# Draft_2.net
KiCad netlist of a schematic drawn in EAGLE
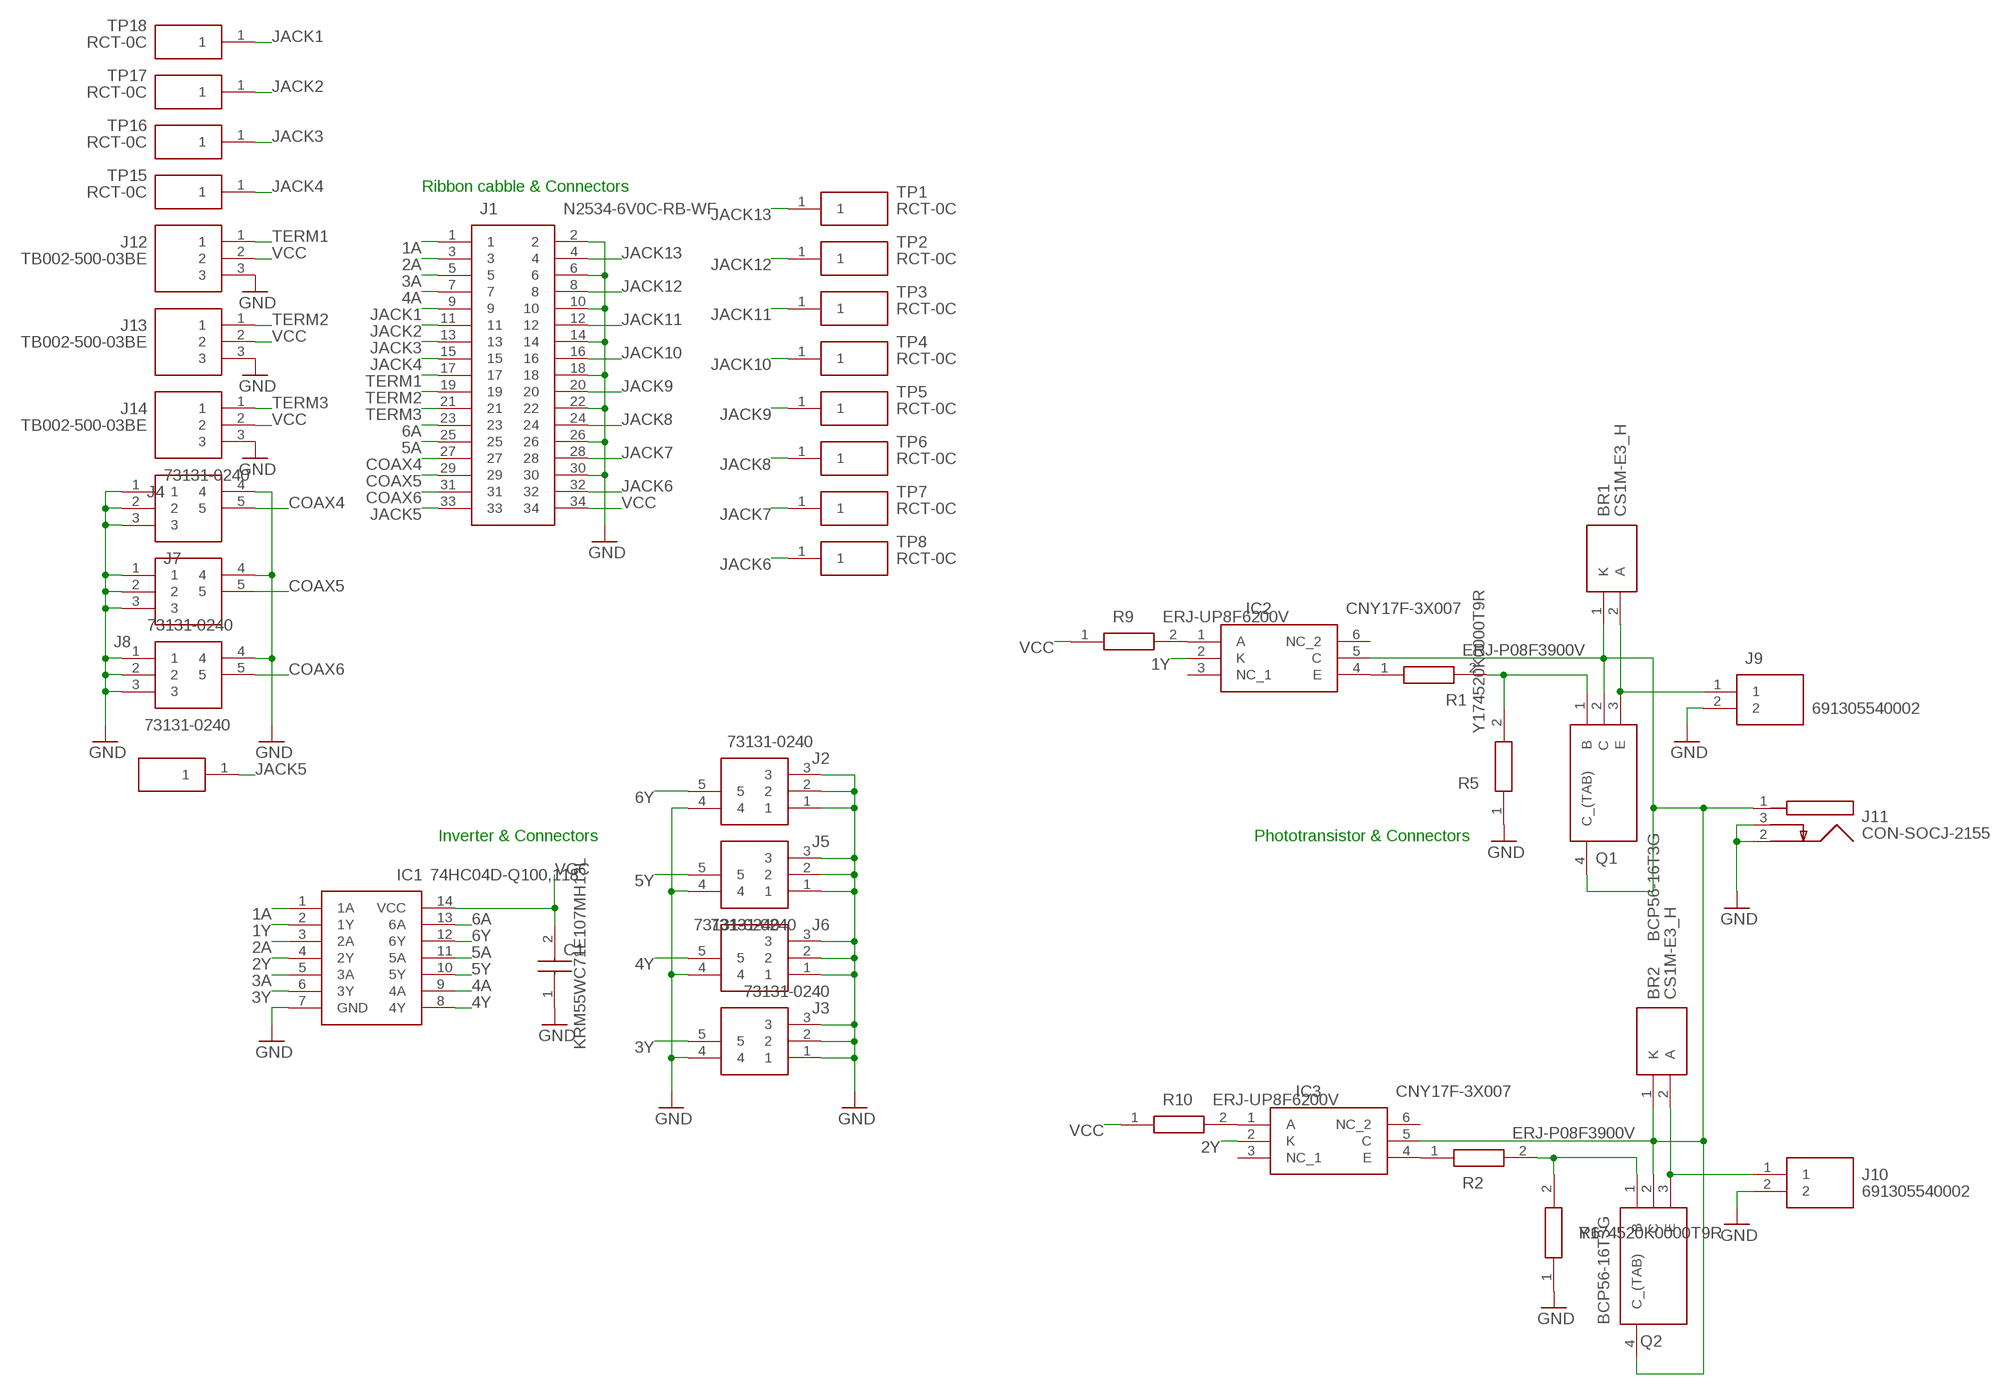
[diagram p0: schematic, sheet 1]

(export (version "E")
  (design (tool "Eeschema 10.0.6"))
  (components
    (comp (ref "BR1")
      (value "CS1M-E3_H")
      (footprint "eagle-import:DIOM5127X229N")
      (fields
        (field (name "MANUFACTURER_PART_NUMBER") "CS1M-E3/H")
        (field (name "MOUSER_PART_NUMBER") "78-CS1M-E3/H")
      )
      (libsource (lib "eagle-import") (part "CS1M-E3_H"))
    )
    (comp (ref "BR2")
      (value "CS1M-E3_H")
      (footprint "eagle-import:DIOM5127X229N")
      (fields
        (field (name "MANUFACTURER_PART_NUMBER") "CS1M-E3/H")
        (field (name "MOUSER_PART_NUMBER") "78-CS1M-E3/H")
      )
      (libsource (lib "eagle-import") (part "CS1M-E3_H"))
    )
    (comp (ref "C1")
      (value "KRM55WC71E107MH13L")
      (footprint "eagle-import:CAPC6153X670N")
      (fields (field (name "MOUSER_PART_NUMBER") "81-KRM55WC71E107MH3L"))
      (libsource (lib "eagle-import") (part "KRM55WC71E107MH13L"))
    )
    (comp (ref "IC1")
      (value "74HC04D-Q100,118")
      (footprint "eagle-import:SOIC127P600X175-14N")
      (fields (field (name "MOUSER_PART_NUMBER") "771-74HC04D-Q100"))
      (libsource (lib "eagle-import") (part "74HC04D-Q100,118"))
    )
    (comp (ref "IC2")
      (value "CNY17F-3X007")
      (footprint "eagle-import:SOP254P1030X440-6N")
      (fields (field (name "MOUSER_PART_NUMBER") "782-CNY17F-3X007"))
      (libsource (lib "eagle-import") (part "CNY17F-3X007"))
    )
    (comp (ref "IC3")
      (value "CNY17F-3X007")
      (footprint "eagle-import:SOP254P1030X440-6N")
      (fields (field (name "MOUSER_PART_NUMBER") "782-CNY17F-3X007"))
      (libsource (lib "eagle-import") (part "CNY17F-3X007"))
    )
    (comp (ref "J1")
      (value "N2534-6V0C-RB-WF")
      (footprint "eagle-import:3M_N2534-6V0C-RB-WF")
      (fields
        (field (name "MOUSER_PART_NUMBER") "517-N2534-6V0C-RB-WF")
        (field (name "RS_PART_NUMBER") "0212650")
      )
      (libsource (lib "eagle-import") (part "N2534-6V0C-RB-WF"))
    )
    (comp (ref "J2")
      (value "73131-0240")
      (footprint "eagle-import:731310240")
      (fields (field (name "MOUSER_PART_NUMBER") "538-73131-0240"))
      (libsource (lib "eagle-import") (part "73131-0240"))
    )
    (comp (ref "J3")
      (value "73131-0240")
      (footprint "eagle-import:731310240")
      (fields (field (name "MOUSER_PART_NUMBER") "538-73131-0240"))
      (libsource (lib "eagle-import") (part "73131-0240"))
    )
    (comp (ref "J4")
      (value "73131-0240")
      (footprint "eagle-import:731310240")
      (fields (field (name "MOUSER_PART_NUMBER") "538-73131-0240"))
      (libsource (lib "eagle-import") (part "73131-0240"))
    )
    (comp (ref "J5")
      (value "73131-0240")
      (footprint "eagle-import:731310240")
      (fields (field (name "MOUSER_PART_NUMBER") "538-73131-0240"))
      (libsource (lib "eagle-import") (part "73131-0240"))
    )
    (comp (ref "J6")
      (value "73131-0240")
      (footprint "eagle-import:731310240")
      (fields (field (name "MOUSER_PART_NUMBER") "538-73131-0240"))
      (libsource (lib "eagle-import") (part "73131-0240"))
    )
    (comp (ref "J7")
      (value "73131-0240")
      (footprint "eagle-import:731310240")
      (fields (field (name "MOUSER_PART_NUMBER") "538-73131-0240"))
      (libsource (lib "eagle-import") (part "73131-0240"))
    )
    (comp (ref "J8")
      (value "73131-0240")
      (footprint "eagle-import:731310240")
      (fields (field (name "MOUSER_PART_NUMBER") "538-73131-0240"))
      (libsource (lib "eagle-import") (part "73131-0240"))
    )
    (comp (ref "J9")
      (value "691305540002")
      (footprint "eagle-import:SHDRRA2W100P0X508_1X2_1216X120")
      (fields (field (name "MOUSER_PART_NUMBER") "710-691305540002"))
      (libsource (lib "eagle-import") (part "691305540002"))
    )
    (comp (ref "J10")
      (value "691305540002")
      (footprint "eagle-import:SHDRRA2W100P0X508_1X2_1216X120")
      (fields (field (name "MOUSER_PART_NUMBER") "710-691305540002"))
      (libsource (lib "eagle-import") (part "691305540002"))
    )
    (comp (ref "J11")
      (value "CON-SOCJ-2155")
      (footprint "eagle-import:CONSOCJ2155")
      (fields (field (name "MOUSER_PART_NUMBER") "992-CON-SOCJ-2155"))
      (libsource (lib "eagle-import") (part "CON-SOCJ-2155"))
    )
    (comp (ref "J12")
      (value "TB002-500-03BE")
      (footprint "eagle-import:SHDR3W100P0X500_1X3_1500X760X1")
      (fields (field (name "MOUSER_PART_NUMBER") "490-TB002-500-03BE"))
      (libsource (lib "eagle-import") (part "TB002-500-03BE"))
    )
    (comp (ref "J13")
      (value "TB002-500-03BE")
      (footprint "eagle-import:SHDR3W100P0X500_1X3_1500X760X1")
      (fields (field (name "MOUSER_PART_NUMBER") "490-TB002-500-03BE"))
      (libsource (lib "eagle-import") (part "TB002-500-03BE"))
    )
    (comp (ref "J14")
      (value "TB002-500-03BE")
      (footprint "eagle-import:SHDR3W100P0X500_1X3_1500X760X1")
      (fields (field (name "MOUSER_PART_NUMBER") "490-TB002-500-03BE"))
      (libsource (lib "eagle-import") (part "TB002-500-03BE"))
    )
    (comp (ref "Q1")
      (value "BCP56-16T3G")
      (footprint "eagle-import:SOT230P700X175-4N")
      (fields
        (field (name "MOUSER_PART_NUMBER") "863-BCP56-16T3G")
        (field (name "RS_PART_NUMBER") "7737633P")
      )
      (libsource (lib "eagle-import") (part "BCP56-16T3G"))
    )
    (comp (ref "Q2")
      (value "BCP56-16T3G")
      (footprint "eagle-import:SOT230P700X175-4N")
      (fields
        (field (name "MOUSER_PART_NUMBER") "863-BCP56-16T3G")
        (field (name "RS_PART_NUMBER") "7737633P")
      )
      (libsource (lib "eagle-import") (part "BCP56-16T3G"))
    )
    (comp (ref "R1")
      (value "ERJ-P08F3900V")
      (footprint "eagle-import:RESC3116X70N")
      (fields (field (name "MOUSER_PART_NUMBER") "667-ERJ-P08F3900V"))
      (libsource (lib "eagle-import") (part "ERJ-P08F3900V"))
    )
    (comp (ref "R2")
      (value "ERJ-P08F3900V")
      (footprint "eagle-import:RESC3116X70N")
      (fields (field (name "MOUSER_PART_NUMBER") "667-ERJ-P08F3900V"))
      (libsource (lib "eagle-import") (part "ERJ-P08F3900V"))
    )
    (comp (ref "R5")
      (value "Y174520K0000T9R")
      (footprint "eagle-import:RESM6032X279N")
      (fields
        (field (name "MOUSER_PART_NUMBER") "71-SMR1DZ20K000TST")
        (field (name "RS_PART_NUMBER") "7637249P")
      )
      (libsource (lib "eagle-import") (part "Y174520K0000T9R"))
    )
    (comp (ref "R6")
      (value "Y174520K0000T9R")
      (footprint "eagle-import:RESM6032X279N")
      (fields
        (field (name "MOUSER_PART_NUMBER") "71-SMR1DZ20K000TST")
        (field (name "RS_PART_NUMBER") "7637249P")
      )
      (libsource (lib "eagle-import") (part "Y174520K0000T9R"))
    )
    (comp (ref "R9")
      (value "ERJ-UP8F6200V")
      (footprint "eagle-import:RESC3116X70N")
      (fields (field (name "MOUSER_PART_NUMBER") "667-ERJ-UP8F6200V"))
      (libsource (lib "eagle-import") (part "ERJ-UP8F6200V"))
    )
    (comp (ref "R10")
      (value "ERJ-UP8F6200V")
      (footprint "eagle-import:RESC3116X70N")
      (fields (field (name "MOUSER_PART_NUMBER") "667-ERJ-UP8F6200V"))
      (libsource (lib "eagle-import") (part "ERJ-UP8F6200V"))
    )
    (comp (ref "TP1")
      (value "RCT-0C")
      (footprint "eagle-import:RCT-0C")
      (fields (field (name "MOUSER_PART_NUMBER") "279-RCT-0C"))
      (libsource (lib "eagle-import") (part "RCT-0C"))
    )
    (comp (ref "TP2")
      (value "RCT-0C")
      (footprint "eagle-import:RCT-0C")
      (fields (field (name "MOUSER_PART_NUMBER") "279-RCT-0C"))
      (libsource (lib "eagle-import") (part "RCT-0C"))
    )
    (comp (ref "TP3")
      (value "RCT-0C")
      (footprint "eagle-import:RCT-0C")
      (fields (field (name "MOUSER_PART_NUMBER") "279-RCT-0C"))
      (libsource (lib "eagle-import") (part "RCT-0C"))
    )
    (comp (ref "TP4")
      (value "RCT-0C")
      (footprint "eagle-import:RCT-0C")
      (fields (field (name "MOUSER_PART_NUMBER") "279-RCT-0C"))
      (libsource (lib "eagle-import") (part "RCT-0C"))
    )
    (comp (ref "TP5")
      (value "RCT-0C")
      (footprint "eagle-import:RCT-0C")
      (fields (field (name "MOUSER_PART_NUMBER") "279-RCT-0C"))
      (libsource (lib "eagle-import") (part "RCT-0C"))
    )
    (comp (ref "TP6")
      (value "RCT-0C")
      (footprint "eagle-import:RCT-0C")
      (fields (field (name "MOUSER_PART_NUMBER") "279-RCT-0C"))
      (libsource (lib "eagle-import") (part "RCT-0C"))
    )
    (comp (ref "TP7")
      (value "RCT-0C")
      (footprint "eagle-import:RCT-0C")
      (fields (field (name "MOUSER_PART_NUMBER") "279-RCT-0C"))
      (libsource (lib "eagle-import") (part "RCT-0C"))
    )
    (comp (ref "TP8")
      (value "RCT-0C")
      (footprint "eagle-import:RCT-0C")
      (fields (field (name "MOUSER_PART_NUMBER") "279-RCT-0C"))
      (libsource (lib "eagle-import") (part "RCT-0C"))
    )
    (comp (ref "TP9")
      (value "RCT-0C")
      (footprint "eagle-import:RCT-0C")
      (fields (field (name "MOUSER_PART_NUMBER") "279-RCT-0C"))
      (libsource (lib "eagle-import") (part "RCT-0C"))
    )
    (comp (ref "TP15")
      (value "RCT-0C")
      (footprint "eagle-import:RCT-0C")
      (fields (field (name "MOUSER_PART_NUMBER") "279-RCT-0C"))
      (libsource (lib "eagle-import") (part "RCT-0C"))
    )
    (comp (ref "TP16")
      (value "RCT-0C")
      (footprint "eagle-import:RCT-0C")
      (fields (field (name "MOUSER_PART_NUMBER") "279-RCT-0C"))
      (libsource (lib "eagle-import") (part "RCT-0C"))
    )
    (comp (ref "TP17")
      (value "RCT-0C")
      (footprint "eagle-import:RCT-0C")
      (fields (field (name "MOUSER_PART_NUMBER") "279-RCT-0C"))
      (libsource (lib "eagle-import") (part "RCT-0C"))
    )
    (comp (ref "TP18")
      (value "RCT-0C")
      (footprint "eagle-import:RCT-0C")
      (fields (field (name "MOUSER_PART_NUMBER") "279-RCT-0C"))
      (libsource (lib "eagle-import") (part "RCT-0C"))
    )
  )
  (nets
    (net (code "1") (name "/1A") (class "Default")
      (node (ref "IC1") (pin "1") (pinfunction "1A_1") (pintype "bidirectional"))
      (node (ref "J1") (pin "1") (pinfunction "1_1") (pintype "bidirectional"))
    )
    (net (code "2") (name "/1Y") (class "Default")
      (node (ref "IC1") (pin "2") (pinfunction "1Y_2") (pintype "bidirectional"))
      (node (ref "IC2") (pin "2") (pinfunction "K_2") (pintype "bidirectional"))
    )
    (net (code "3") (name "/2A") (class "Default")
      (node (ref "IC1") (pin "3") (pinfunction "2A_3") (pintype "bidirectional"))
      (node (ref "J1") (pin "3") (pinfunction "3_3") (pintype "bidirectional"))
    )
    (net (code "4") (name "/2Y") (class "Default")
      (node (ref "IC1") (pin "4") (pinfunction "2Y_4") (pintype "bidirectional"))
      (node (ref "IC3") (pin "2") (pinfunction "K_2") (pintype "bidirectional"))
    )
    (net (code "5") (name "/3A") (class "Default")
      (node (ref "IC1") (pin "5") (pinfunction "3A_5") (pintype "bidirectional"))
      (node (ref "J1") (pin "5") (pinfunction "5_5") (pintype "bidirectional"))
    )
    (net (code "6") (name "/3Y") (class "Default")
      (node (ref "IC1") (pin "6") (pinfunction "3Y_6") (pintype "bidirectional"))
      (node (ref "J3") (pin "5") (pinfunction "5_5") (pintype "bidirectional"))
    )
    (net (code "7") (name "/4A") (class "Default")
      (node (ref "IC1") (pin "9") (pinfunction "4A_9") (pintype "bidirectional"))
      (node (ref "J1") (pin "7") (pinfunction "7_7") (pintype "bidirectional"))
    )
    (net (code "8") (name "/4Y") (class "Default")
      (node (ref "IC1") (pin "8") (pinfunction "4Y_8") (pintype "bidirectional"))
      (node (ref "J6") (pin "5") (pinfunction "5_5") (pintype "bidirectional"))
    )
    (net (code "9") (name "/5A") (class "Default")
      (node (ref "IC1") (pin "11") (pinfunction "5A_11") (pintype "bidirectional"))
      (node (ref "J1") (pin "25") (pinfunction "25_25") (pintype "bidirectional"))
    )
    (net (code "10") (name "/5Y") (class "Default")
      (node (ref "IC1") (pin "10") (pinfunction "5Y_10") (pintype "bidirectional"))
      (node (ref "J5") (pin "5") (pinfunction "5_5") (pintype "bidirectional"))
    )
    (net (code "11") (name "/6A") (class "Default")
      (node (ref "IC1") (pin "13") (pinfunction "6A_13") (pintype "bidirectional"))
      (node (ref "J1") (pin "23") (pinfunction "23_23") (pintype "bidirectional"))
    )
    (net (code "12") (name "/6Y") (class "Default")
      (node (ref "IC1") (pin "12") (pinfunction "6Y_12") (pintype "bidirectional"))
      (node (ref "J2") (pin "5") (pinfunction "5_5") (pintype "bidirectional"))
    )
    (net (code "13") (name "/COAX4") (class "Default")
      (node (ref "J1") (pin "27") (pinfunction "27_27") (pintype "bidirectional"))
      (node (ref "J4") (pin "5") (pinfunction "5_5") (pintype "bidirectional"))
    )
    (net (code "14") (name "/COAX5") (class "Default")
      (node (ref "J1") (pin "29") (pinfunction "29_29") (pintype "bidirectional"))
      (node (ref "J7") (pin "5") (pinfunction "5_5") (pintype "bidirectional"))
    )
    (net (code "15") (name "/COAX6") (class "Default")
      (node (ref "J1") (pin "31") (pinfunction "31_31") (pintype "bidirectional"))
      (node (ref "J8") (pin "5") (pinfunction "5_5") (pintype "bidirectional"))
    )
    (net (code "16") (name "/JACK1") (class "Default")
      (node (ref "J1") (pin "9") (pinfunction "9_9") (pintype "bidirectional"))
      (node (ref "TP18") (pin "1") (pinfunction "1_1") (pintype "bidirectional"))
    )
    (net (code "17") (name "/JACK2") (class "Default")
      (node (ref "J1") (pin "11") (pinfunction "11_11") (pintype "bidirectional"))
      (node (ref "TP17") (pin "1") (pinfunction "1_1") (pintype "bidirectional"))
    )
    (net (code "18") (name "/JACK3") (class "Default")
      (node (ref "J1") (pin "13") (pinfunction "13_13") (pintype "bidirectional"))
      (node (ref "TP16") (pin "1") (pinfunction "1_1") (pintype "bidirectional"))
    )
    (net (code "19") (name "/JACK4") (class "Default")
      (node (ref "J1") (pin "15") (pinfunction "15_15") (pintype "bidirectional"))
      (node (ref "TP15") (pin "1") (pinfunction "1_1") (pintype "bidirectional"))
    )
    (net (code "20") (name "/JACK5") (class "Default")
      (node (ref "J1") (pin "33") (pinfunction "33_33") (pintype "bidirectional"))
      (node (ref "TP9") (pin "1") (pinfunction "1_1") (pintype "bidirectional"))
    )
    (net (code "21") (name "/JACK6") (class "Default")
      (node (ref "J1") (pin "32") (pinfunction "32_32") (pintype "bidirectional"))
      (node (ref "TP8") (pin "1") (pinfunction "1_1") (pintype "bidirectional"))
    )
    (net (code "22") (name "/JACK7") (class "Default")
      (node (ref "J1") (pin "28") (pinfunction "28_28") (pintype "bidirectional"))
      (node (ref "TP7") (pin "1") (pinfunction "1_1") (pintype "bidirectional"))
    )
    (net (code "23") (name "/JACK8") (class "Default")
      (node (ref "J1") (pin "24") (pinfunction "24_24") (pintype "bidirectional"))
      (node (ref "TP6") (pin "1") (pinfunction "1_1") (pintype "bidirectional"))
    )
    (net (code "24") (name "/JACK9") (class "Default")
      (node (ref "J1") (pin "20") (pinfunction "20_20") (pintype "bidirectional"))
      (node (ref "TP5") (pin "1") (pinfunction "1_1") (pintype "bidirectional"))
    )
    (net (code "25") (name "/JACK10") (class "Default")
      (node (ref "J1") (pin "16") (pinfunction "16_16") (pintype "bidirectional"))
      (node (ref "TP4") (pin "1") (pinfunction "1_1") (pintype "bidirectional"))
    )
    (net (code "26") (name "/JACK11") (class "Default")
      (node (ref "J1") (pin "12") (pinfunction "12_12") (pintype "bidirectional"))
      (node (ref "TP3") (pin "1") (pinfunction "1_1") (pintype "bidirectional"))
    )
    (net (code "27") (name "/JACK12") (class "Default")
      (node (ref "J1") (pin "8") (pinfunction "8_8") (pintype "bidirectional"))
      (node (ref "TP2") (pin "1") (pinfunction "1_1") (pintype "bidirectional"))
    )
    (net (code "28") (name "/JACK13") (class "Default")
      (node (ref "J1") (pin "4") (pinfunction "4_4") (pintype "bidirectional"))
      (node (ref "TP1") (pin "1") (pinfunction "1_1") (pintype "bidirectional"))
    )
    (net (code "29") (name "/TERM1") (class "Default")
      (node (ref "J1") (pin "17") (pinfunction "17_17") (pintype "bidirectional"))
      (node (ref "J12") (pin "1") (pinfunction "1_1") (pintype "bidirectional"))
    )
    (net (code "30") (name "/TERM2") (class "Default")
      (node (ref "J1") (pin "19") (pinfunction "19_19") (pintype "bidirectional"))
      (node (ref "J13") (pin "1") (pinfunction "1_1") (pintype "bidirectional"))
    )
    (net (code "31") (name "/TERM3") (class "Default")
      (node (ref "J1") (pin "21") (pinfunction "21_21") (pintype "bidirectional"))
      (node (ref "J14") (pin "1") (pinfunction "1_1") (pintype "bidirectional"))
    )
    (net (code "32") (name "/VCC") (class "Default")
      (node (ref "C1") (pin "2") (pinfunction "2_2") (pintype "bidirectional"))
      (node (ref "IC1") (pin "14") (pinfunction "VCC_14") (pintype "bidirectional"))
      (node (ref "J1") (pin "34") (pinfunction "34_34") (pintype "bidirectional"))
      (node (ref "J12") (pin "2") (pinfunction "2_2") (pintype "bidirectional"))
      (node (ref "J13") (pin "2") (pinfunction "2_2") (pintype "bidirectional"))
      (node (ref "J14") (pin "2") (pinfunction "2_2") (pintype "bidirectional"))
      (node (ref "R10") (pin "1") (pinfunction "1_1") (pintype "bidirectional"))
      (node (ref "R9") (pin "1") (pinfunction "1_1") (pintype "bidirectional"))
    )
    (net (code "33") (name "GND") (class "Default")
      (node (ref "C1") (pin "1") (pinfunction "1_1") (pintype "bidirectional"))
      (node (ref "IC1") (pin "7") (pinfunction "GND_7") (pintype "bidirectional"))
      (node (ref "J1") (pin "10") (pinfunction "10_10") (pintype "bidirectional"))
      (node (ref "J1") (pin "14") (pinfunction "14_14") (pintype "bidirectional"))
      (node (ref "J1") (pin "18") (pinfunction "18_18") (pintype "bidirectional"))
      (node (ref "J1") (pin "2") (pinfunction "2_2") (pintype "bidirectional"))
      (node (ref "J1") (pin "22") (pinfunction "22_22") (pintype "bidirectional"))
      (node (ref "J1") (pin "26") (pinfunction "26_26") (pintype "bidirectional"))
      (node (ref "J1") (pin "30") (pinfunction "30_30") (pintype "bidirectional"))
      (node (ref "J1") (pin "6") (pinfunction "6_6") (pintype "bidirectional"))
      (node (ref "J10") (pin "2") (pinfunction "2_2") (pintype "bidirectional"))
      (node (ref "J11") (pin "2") (pinfunction "2_2") (pintype "bidirectional"))
      (node (ref "J11") (pin "3") (pinfunction "3_3") (pintype "bidirectional"))
      (node (ref "J12") (pin "3") (pinfunction "3_3") (pintype "bidirectional"))
      (node (ref "J13") (pin "3") (pinfunction "3_3") (pintype "bidirectional"))
      (node (ref "J14") (pin "3") (pinfunction "3_3") (pintype "bidirectional"))
      (node (ref "J2") (pin "1") (pinfunction "1_1") (pintype "bidirectional"))
      (node (ref "J2") (pin "2") (pinfunction "2_2") (pintype "bidirectional"))
      (node (ref "J2") (pin "3") (pinfunction "3_3") (pintype "bidirectional"))
      (node (ref "J2") (pin "4") (pinfunction "4_4") (pintype "bidirectional"))
      (node (ref "J3") (pin "1") (pinfunction "1_1") (pintype "bidirectional"))
      (node (ref "J3") (pin "2") (pinfunction "2_2") (pintype "bidirectional"))
      (node (ref "J3") (pin "3") (pinfunction "3_3") (pintype "bidirectional"))
      (node (ref "J3") (pin "4") (pinfunction "4_4") (pintype "bidirectional"))
      (node (ref "J4") (pin "1") (pinfunction "1_1") (pintype "bidirectional"))
      (node (ref "J4") (pin "2") (pinfunction "2_2") (pintype "bidirectional"))
      (node (ref "J4") (pin "3") (pinfunction "3_3") (pintype "bidirectional"))
      (node (ref "J4") (pin "4") (pinfunction "4_4") (pintype "bidirectional"))
      (node (ref "J5") (pin "1") (pinfunction "1_1") (pintype "bidirectional"))
      (node (ref "J5") (pin "2") (pinfunction "2_2") (pintype "bidirectional"))
      (node (ref "J5") (pin "3") (pinfunction "3_3") (pintype "bidirectional"))
      (node (ref "J5") (pin "4") (pinfunction "4_4") (pintype "bidirectional"))
      (node (ref "J6") (pin "1") (pinfunction "1_1") (pintype "bidirectional"))
      (node (ref "J6") (pin "2") (pinfunction "2_2") (pintype "bidirectional"))
      (node (ref "J6") (pin "3") (pinfunction "3_3") (pintype "bidirectional"))
      (node (ref "J6") (pin "4") (pinfunction "4_4") (pintype "bidirectional"))
      (node (ref "J7") (pin "1") (pinfunction "1_1") (pintype "bidirectional"))
      (node (ref "J7") (pin "2") (pinfunction "2_2") (pintype "bidirectional"))
      (node (ref "J7") (pin "3") (pinfunction "3_3") (pintype "bidirectional"))
      (node (ref "J7") (pin "4") (pinfunction "4_4") (pintype "bidirectional"))
      (node (ref "J8") (pin "1") (pinfunction "1_1") (pintype "bidirectional"))
      (node (ref "J8") (pin "2") (pinfunction "2_2") (pintype "bidirectional"))
      (node (ref "J8") (pin "3") (pinfunction "3_3") (pintype "bidirectional"))
      (node (ref "J8") (pin "4") (pinfunction "4_4") (pintype "bidirectional"))
      (node (ref "J9") (pin "2") (pinfunction "2_2") (pintype "bidirectional"))
      (node (ref "R5") (pin "1") (pinfunction "1_1") (pintype "bidirectional"))
      (node (ref "R6") (pin "1") (pinfunction "1_1") (pintype "bidirectional"))
    )
    (net (code "34") (name "Net-(BR1-A)") (class "Default")
      (node (ref "BR1") (pin "2") (pinfunction "A_2") (pintype "bidirectional"))
      (node (ref "J9") (pin "1") (pinfunction "1_1") (pintype "bidirectional"))
      (node (ref "Q1") (pin "3") (pinfunction "E_3") (pintype "bidirectional"))
    )
    (net (code "35") (name "Net-(BR1-K)") (class "Default")
      (node (ref "BR1") (pin "1") (pinfunction "K_1") (pintype "bidirectional"))
      (node (ref "BR2") (pin "1") (pinfunction "K_1") (pintype "bidirectional"))
      (node (ref "IC2") (pin "5") (pinfunction "C_5") (pintype "bidirectional"))
      (node (ref "IC3") (pin "5") (pinfunction "C_5") (pintype "bidirectional"))
      (node (ref "J11") (pin "1") (pinfunction "1_1") (pintype "bidirectional"))
      (node (ref "Q1") (pin "2") (pinfunction "C_2") (pintype "bidirectional"))
      (node (ref "Q1") (pin "4") (pinfunction "C_(TAB)_4") (pintype "bidirectional"))
      (node (ref "Q2") (pin "2") (pinfunction "C_2") (pintype "bidirectional"))
      (node (ref "Q2") (pin "4") (pinfunction "C_(TAB)_4") (pintype "bidirectional"))
    )
    (net (code "36") (name "Net-(BR2-A)") (class "Default")
      (node (ref "BR2") (pin "2") (pinfunction "A_2") (pintype "bidirectional"))
      (node (ref "J10") (pin "1") (pinfunction "1_1") (pintype "bidirectional"))
      (node (ref "Q2") (pin "3") (pinfunction "E_3") (pintype "bidirectional"))
    )
    (net (code "37") (name "Net-(IC2-A)") (class "Default")
      (node (ref "IC2") (pin "1") (pinfunction "A_1") (pintype "bidirectional"))
      (node (ref "R9") (pin "2") (pinfunction "2_2") (pintype "bidirectional"))
    )
    (net (code "38") (name "Net-(IC2-E)") (class "Default")
      (node (ref "IC2") (pin "4") (pinfunction "E_4") (pintype "bidirectional"))
      (node (ref "R1") (pin "1") (pinfunction "1_1") (pintype "bidirectional"))
    )
    (net (code "39") (name "Net-(IC3-A)") (class "Default")
      (node (ref "IC3") (pin "1") (pinfunction "A_1") (pintype "bidirectional"))
      (node (ref "R10") (pin "2") (pinfunction "2_2") (pintype "bidirectional"))
    )
    (net (code "40") (name "Net-(IC3-E)") (class "Default")
      (node (ref "IC3") (pin "4") (pinfunction "E_4") (pintype "bidirectional"))
      (node (ref "R2") (pin "1") (pinfunction "1_1") (pintype "bidirectional"))
    )
    (net (code "41") (name "Net-(Q1-B)") (class "Default")
      (node (ref "Q1") (pin "1") (pinfunction "B_1") (pintype "bidirectional"))
      (node (ref "R1") (pin "2") (pinfunction "2_2") (pintype "bidirectional"))
      (node (ref "R5") (pin "2") (pinfunction "2_2") (pintype "bidirectional"))
    )
    (net (code "42") (name "Net-(Q2-B)") (class "Default")
      (node (ref "Q2") (pin "1") (pinfunction "B_1") (pintype "bidirectional"))
      (node (ref "R2") (pin "2") (pinfunction "2_2") (pintype "bidirectional"))
      (node (ref "R6") (pin "2") (pinfunction "2_2") (pintype "bidirectional"))
    )
    (net (code "43") (name "unconnected-(IC2-NC_1-Pad3)") (class "Default")
      (node (ref "IC2") (pin "3") (pinfunction "NC_1_3") (pintype "bidirectional"))
    )
    (net (code "44") (name "unconnected-(IC2-NC_2-Pad6)") (class "Default")
      (node (ref "IC2") (pin "6") (pinfunction "NC_2_6") (pintype "bidirectional"))
    )
    (net (code "45") (name "unconnected-(IC3-NC_1-Pad3)") (class "Default")
      (node (ref "IC3") (pin "3") (pinfunction "NC_1_3") (pintype "bidirectional"))
    )
    (net (code "46") (name "unconnected-(IC3-NC_2-Pad6)") (class "Default")
      (node (ref "IC3") (pin "6") (pinfunction "NC_2_6") (pintype "bidirectional"))
    )
  )
)
